# EEZ_PSU_post-regulator_r4B44_SS.net
KiCad netlist of a schematic drawn in EAGLE
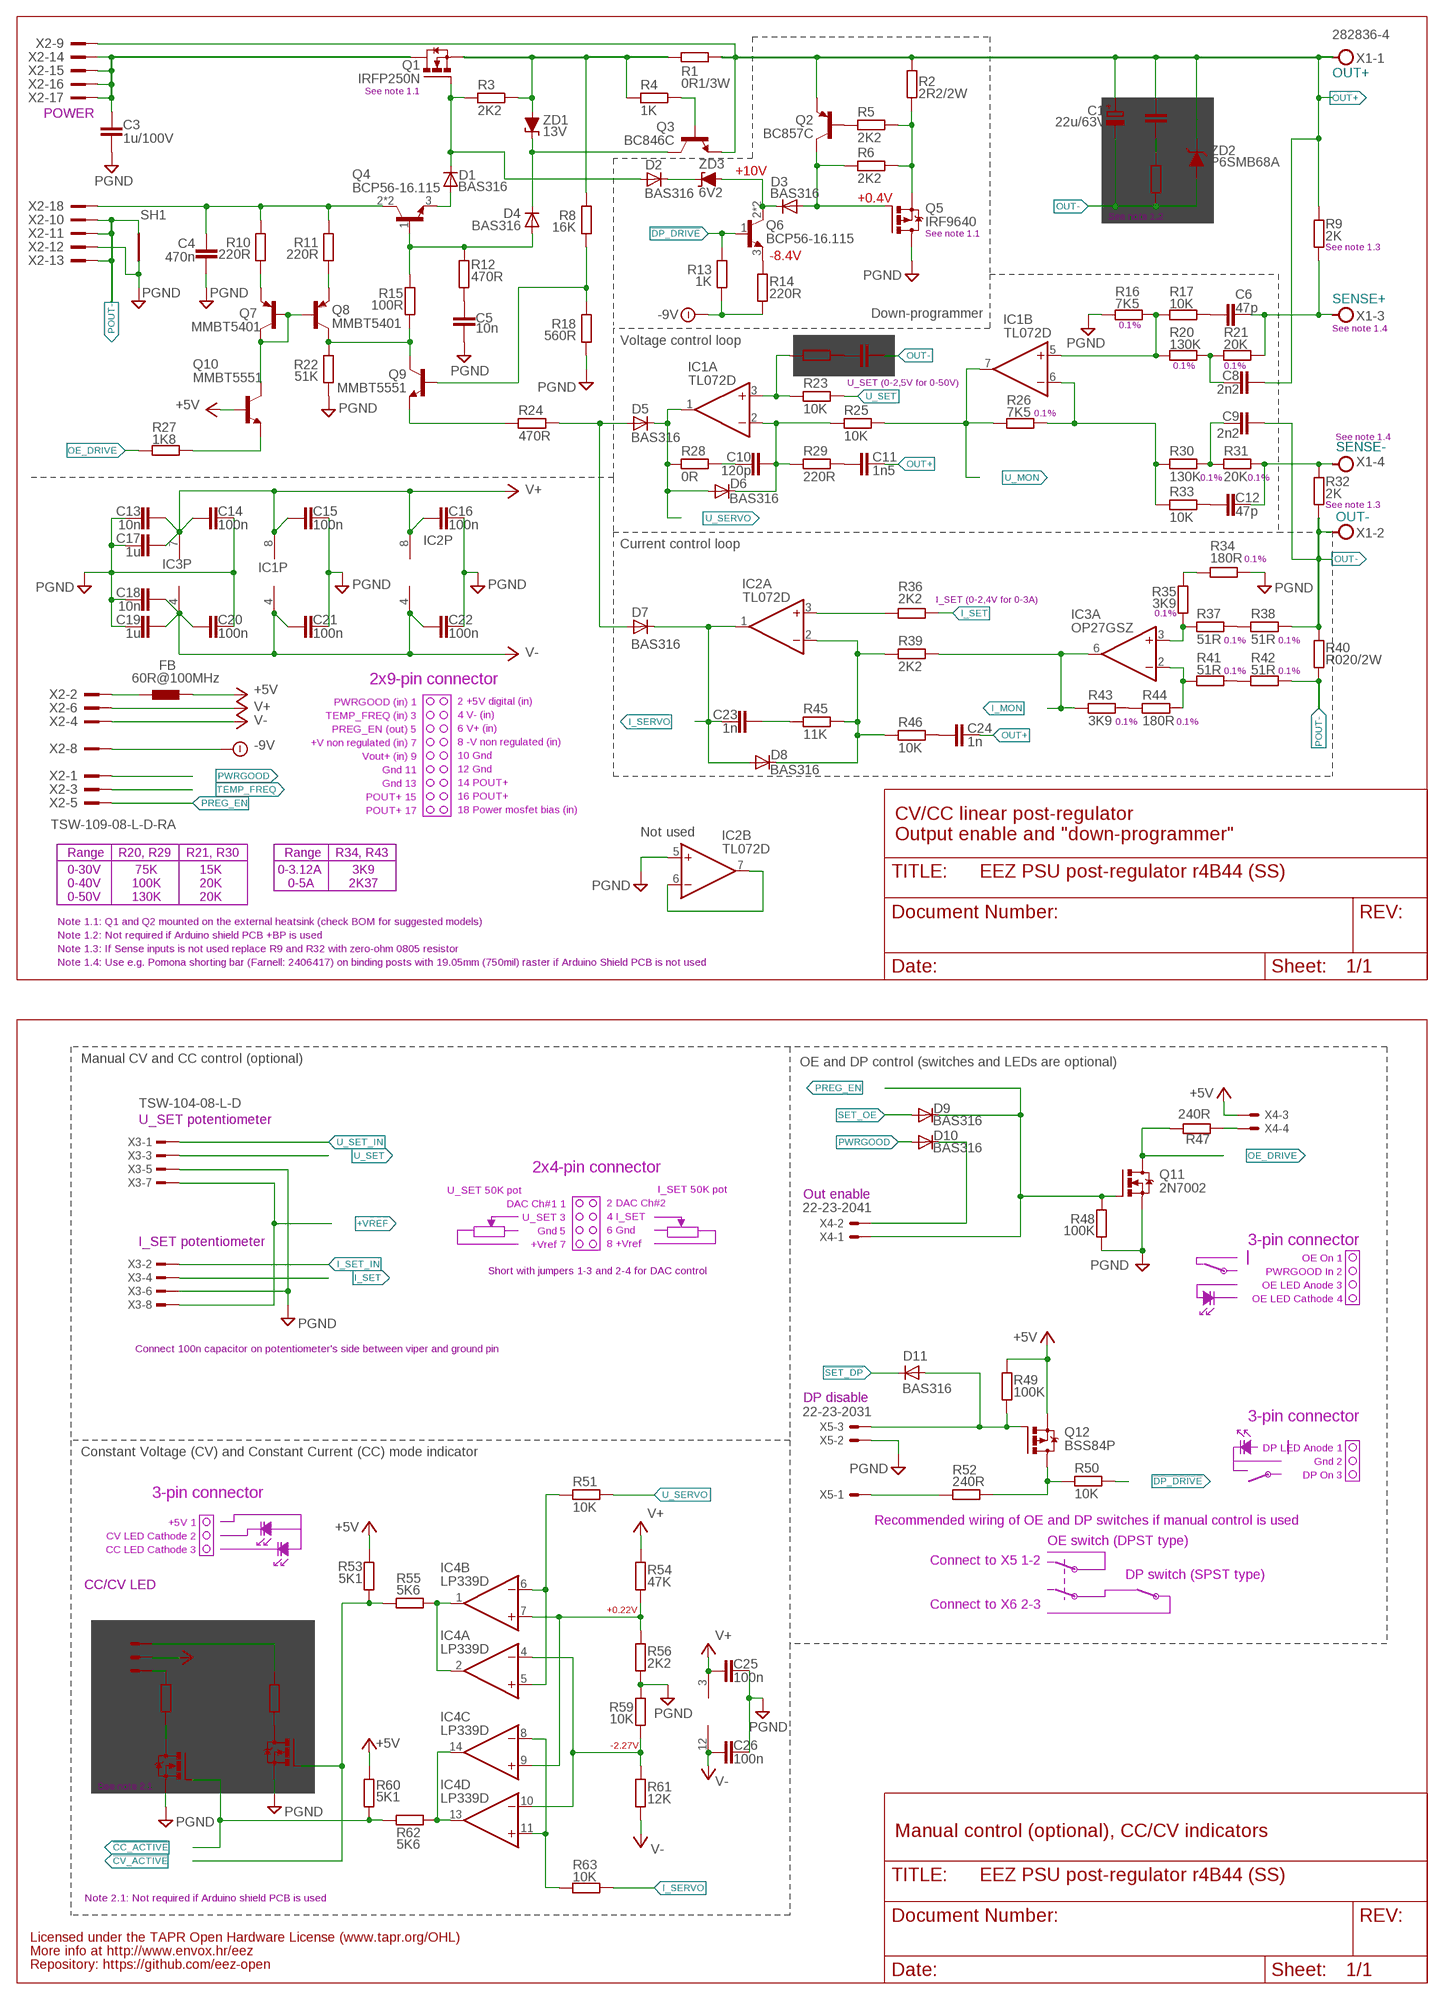
[diagram p0: schematic, sheet 1, part 1 of 2]
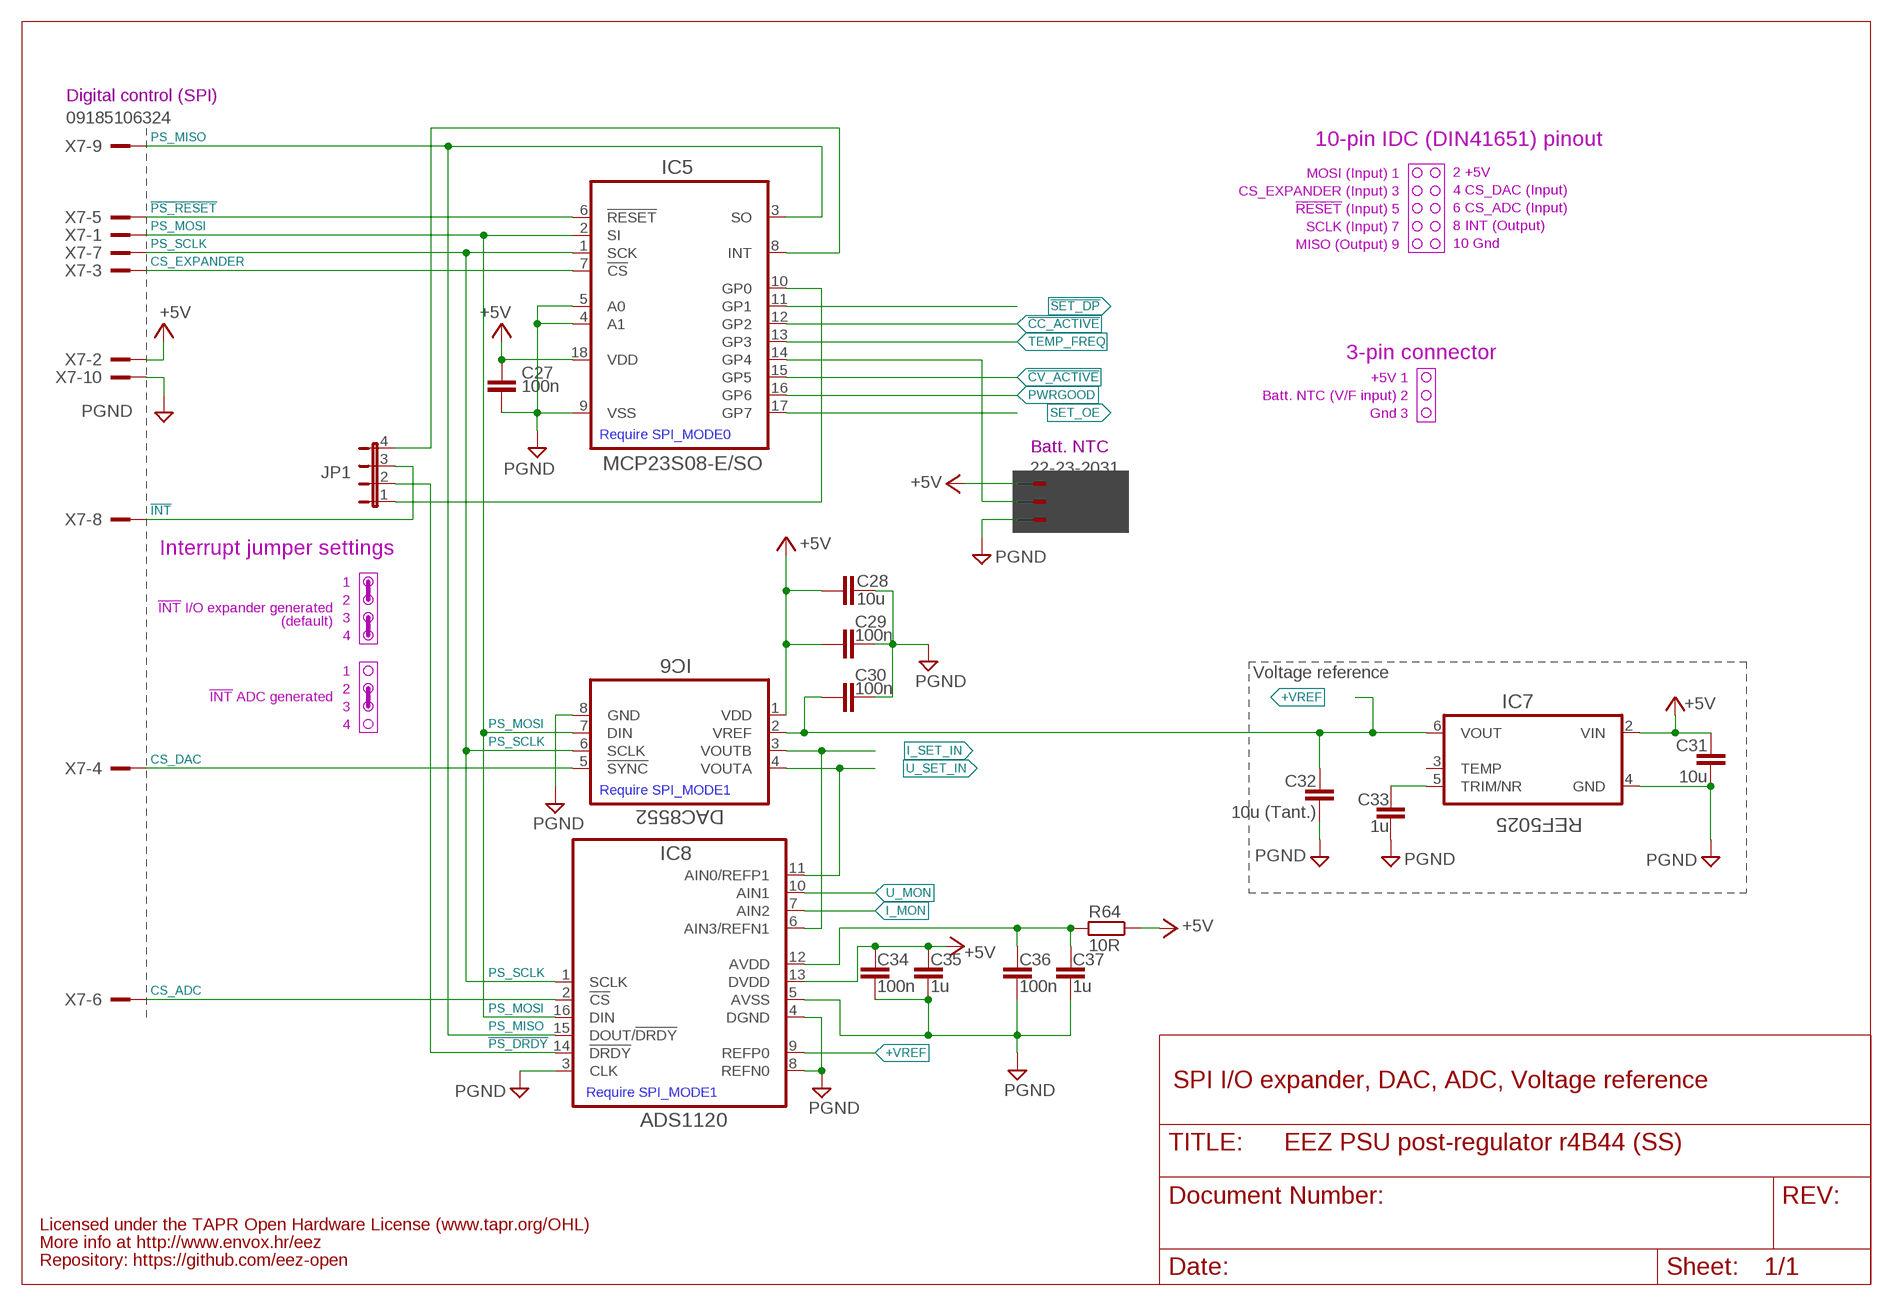
[diagram p1: schematic, sheet 1, part 2 of 2]

(export (version "E")
  (design (tool "Eeschema 10.0.6"))
  (components
    (comp (ref "C1")
      (value "22u/63V")
      (footprint "eagle-import:CAPAE660X610N_COMBO2")
      (libsource (lib "eagle-import") (part "ECAPEEEFK+2.5MM"))
    )
    (comp (ref "C2")
      (value "470n")
      (footprint "eagle-import:C1812")
      (libsource (lib "eagle-import") (part "C-EUC1812"))
    )
    (comp (ref "C3")
      (value "1u/100V")
      (footprint "eagle-import:C1206")
      (libsource (lib "eagle-import") (part "C-EUC1206"))
    )
    (comp (ref "C4")
      (value "470n")
      (footprint "eagle-import:C1812")
      (libsource (lib "eagle-import") (part "C-EUC1812"))
    )
    (comp (ref "C5")
      (value "10n")
      (footprint "eagle-import:C0805")
      (libsource (lib "eagle-import") (part "C-EUC0805"))
    )
    (comp (ref "C6")
      (value "47p")
      (footprint "eagle-import:C0805")
      (libsource (lib "eagle-import") (part "C-EUC0805"))
    )
    (comp (ref "C7")
      (value "1n5")
      (footprint "eagle-import:C0805")
      (libsource (lib "eagle-import") (part "C-EUC0805"))
    )
    (comp (ref "C8")
      (value "2n2")
      (footprint "eagle-import:C0805")
      (libsource (lib "eagle-import") (part "C-EUC0805"))
    )
    (comp (ref "C9")
      (value "2n2")
      (footprint "eagle-import:C0805")
      (libsource (lib "eagle-import") (part "C-EUC0805"))
    )
    (comp (ref "C10")
      (value "120p")
      (footprint "eagle-import:C0805")
      (libsource (lib "eagle-import") (part "C-EUC0805"))
    )
    (comp (ref "C11")
      (value "1n5")
      (footprint "eagle-import:C0805")
      (libsource (lib "eagle-import") (part "C-EUC0805"))
    )
    (comp (ref "C12")
      (value "47p")
      (footprint "eagle-import:C0805")
      (libsource (lib "eagle-import") (part "C-EUC0805"))
    )
    (comp (ref "C13")
      (value "10n")
      (footprint "eagle-import:C0805")
      (libsource (lib "eagle-import") (part "C-EUC0805"))
    )
    (comp (ref "C14")
      (value "100n")
      (footprint "eagle-import:C0603")
      (libsource (lib "eagle-import") (part "C-EUC0603"))
    )
    (comp (ref "C15")
      (value "100n")
      (footprint "eagle-import:C0603")
      (libsource (lib "eagle-import") (part "C-EUC0603"))
    )
    (comp (ref "C16")
      (value "100n")
      (footprint "eagle-import:C0603")
      (libsource (lib "eagle-import") (part "C-EUC0603"))
    )
    (comp (ref "C17")
      (value "1u")
      (footprint "eagle-import:C0805")
      (libsource (lib "eagle-import") (part "C-EUC0805"))
    )
    (comp (ref "C18")
      (value "10n")
      (footprint "eagle-import:C0805")
      (libsource (lib "eagle-import") (part "C-EUC0805"))
    )
    (comp (ref "C19")
      (value "1u")
      (footprint "eagle-import:C0805")
      (libsource (lib "eagle-import") (part "C-EUC0805"))
    )
    (comp (ref "C20")
      (value "100n")
      (footprint "eagle-import:C0603")
      (libsource (lib "eagle-import") (part "C-EUC0603"))
    )
    (comp (ref "C21")
      (value "100n")
      (footprint "eagle-import:C0603")
      (libsource (lib "eagle-import") (part "C-EUC0603"))
    )
    (comp (ref "C22")
      (value "100n")
      (footprint "eagle-import:C0603")
      (libsource (lib "eagle-import") (part "C-EUC0603"))
    )
    (comp (ref "C23")
      (value "1n")
      (footprint "eagle-import:C0805")
      (libsource (lib "eagle-import") (part "C-EUC0805"))
    )
    (comp (ref "C24")
      (value "1n")
      (footprint "eagle-import:C0805")
      (libsource (lib "eagle-import") (part "C-EUC0805"))
    )
    (comp (ref "C25")
      (value "100n")
      (footprint "eagle-import:C0603")
      (libsource (lib "eagle-import") (part "C-EUC0603"))
    )
    (comp (ref "C26")
      (value "100n")
      (footprint "eagle-import:C0603")
      (libsource (lib "eagle-import") (part "C-EUC0603"))
    )
    (comp (ref "C27")
      (value "100n")
      (footprint "eagle-import:C0603")
      (libsource (lib "eagle-import") (part "C-EUC0603"))
    )
    (comp (ref "C28")
      (value "10u")
      (footprint "eagle-import:C1206")
      (libsource (lib "eagle-import") (part "C-EUC1206"))
    )
    (comp (ref "C29")
      (value "100n")
      (footprint "eagle-import:C0603")
      (libsource (lib "eagle-import") (part "C-EUC0603"))
    )
    (comp (ref "C30")
      (value "100n")
      (footprint "eagle-import:C0603")
      (libsource (lib "eagle-import") (part "C-EUC0603"))
    )
    (comp (ref "C31")
      (value "10u")
      (footprint "eagle-import:C1206")
      (libsource (lib "eagle-import") (part "C-EUC1206"))
    )
    (comp (ref "C32")
      (value "10u (Tant.)")
      (footprint "eagle-import:C1206")
      (libsource (lib "eagle-import") (part "C-EUC1206"))
    )
    (comp (ref "C33")
      (value "1u")
      (footprint "eagle-import:C0805")
      (libsource (lib "eagle-import") (part "C-EUC0805"))
    )
    (comp (ref "C34")
      (value "100n")
      (footprint "eagle-import:C0603")
      (libsource (lib "eagle-import") (part "C-EUC0603"))
    )
    (comp (ref "C35")
      (value "1u")
      (footprint "eagle-import:C0805")
      (libsource (lib "eagle-import") (part "C-EUC0805"))
    )
    (comp (ref "C36")
      (value "100n")
      (footprint "eagle-import:C0603")
      (libsource (lib "eagle-import") (part "C-EUC0603"))
    )
    (comp (ref "C37")
      (value "1u")
      (footprint "eagle-import:C0805")
      (libsource (lib "eagle-import") (part "C-EUC0805"))
    )
    (comp (ref "D1")
      (value "BAS316")
      (footprint "eagle-import:SOD323-W")
      (libsource (lib "eagle-import") (part "DIODE-SOD323-W"))
    )
    (comp (ref "D2")
      (value "BAS316")
      (footprint "eagle-import:SOD323-W")
      (libsource (lib "eagle-import") (part "DIODE-SOD323-W"))
    )
    (comp (ref "D3")
      (value "BAS316")
      (footprint "eagle-import:SOD323-W")
      (libsource (lib "eagle-import") (part "DIODE-SOD323-W"))
    )
    (comp (ref "D4")
      (value "BAS316")
      (footprint "eagle-import:SOD323-W")
      (libsource (lib "eagle-import") (part "DIODE-SOD323-W"))
    )
    (comp (ref "D5")
      (value "BAS316")
      (footprint "eagle-import:SOD323-W")
      (libsource (lib "eagle-import") (part "DIODE-SOD323-W"))
    )
    (comp (ref "D6")
      (value "BAS316")
      (footprint "eagle-import:SOD323-W")
      (libsource (lib "eagle-import") (part "DIODE-SOD323-W"))
    )
    (comp (ref "D7")
      (value "BAS316")
      (footprint "eagle-import:SOD323-W")
      (libsource (lib "eagle-import") (part "DIODE-SOD323-W"))
    )
    (comp (ref "D8")
      (value "BAS316")
      (footprint "eagle-import:SOD323-W")
      (libsource (lib "eagle-import") (part "DIODE-SOD323-W"))
    )
    (comp (ref "D9")
      (value "BAS316")
      (footprint "eagle-import:SOD323-W")
      (libsource (lib "eagle-import") (part "DIODE-SOD323-W"))
    )
    (comp (ref "D10")
      (value "BAS316")
      (footprint "eagle-import:SOD323-W")
      (libsource (lib "eagle-import") (part "DIODE-SOD323-W"))
    )
    (comp (ref "D11")
      (value "BAS316")
      (footprint "eagle-import:SOD323-W")
      (libsource (lib "eagle-import") (part "DIODE-SOD323-W"))
    )
    (comp (ref "FB")
      (value "60R@100MHz")
      (footprint "eagle-import:BEAD0603")
      (libsource (lib "eagle-import") (part "FERRITE_BEAD0603"))
    )
    (comp (ref "IC1")
      (value "TL072D")
      (footprint "eagle-import:SOIC127P600X173-8N")
      (libsource (lib "eagle-import") (part "TL072SOIC8"))
    )
    (comp (ref "IC2")
      (value "TL072D")
      (footprint "eagle-import:SOIC127P600X173-8N")
      (libsource (lib "eagle-import") (part "TL072SOIC8"))
    )
    (comp (ref "IC3")
      (value "OP27GSZ")
      (footprint "eagle-import:SOIC127P600X173-8N")
      (libsource (lib "eagle-import") (part "OP27GSZSO8"))
    )
    (comp (ref "IC4")
      (value "LP339D")
      (footprint "eagle-import:SO14")
      (libsource (lib "eagle-import") (part "LM339D"))
    )
    (comp (ref "IC5")
      (value "MCP23S08-E/SO")
      (footprint "eagle-import:SOIC127P1030X265-18N")
      (libsource (lib "eagle-import") (part "MCP23S08"))
    )
    (comp (ref "IC6")
      (value "DAC8552")
      (footprint "eagle-import:DGK8-M")
      (libsource (lib "eagle-import") (part "DAC8552_DGK_8M"))
    )
    (comp (ref "IC7")
      (value "REF5025")
      (footprint "eagle-import:SOIC127P600X175-8N")
      (libsource (lib "eagle-import") (part "REF50XX"))
    )
    (comp (ref "IC8")
      (value "ADS1120")
      (footprint "eagle-import:PW(R-PDSO-G16)")
      (libsource (lib "eagle-import") (part "ADS1120TSSOP-16"))
    )
    (comp (ref "JP1")
      (value "JP4E")
      (footprint "eagle-import:JP4")
      (libsource (lib "eagle-import") (part "JP4E"))
    )
    (comp (ref "Q1")
      (value "IRFP250N")
      (footprint "eagle-import:TO247BV")
      (libsource (lib "eagle-import") (part "IRFP240"))
    )
    (comp (ref "Q2")
      (value "BC857C")
      (footprint "eagle-import:SOT23-BEC")
      (libsource (lib "eagle-import") (part "-PNP-SOT23-BECBC857C"))
    )
    (comp (ref "Q3")
      (value "BC846C")
      (footprint "eagle-import:SOT23-BEC")
      (libsource (lib "eagle-import") (part "-NPN-SOT23-BECBC846B"))
    )
    (comp (ref "Q4")
      (value "BCP56-16.115")
      (footprint "eagle-import:SOT230P700X180-4N")
      (libsource (lib "eagle-import") (part "BCP56"))
    )
    (comp (ref "Q5")
      (value "IRF9640")
      (footprint "eagle-import:TO220B-VMOS")
      (libsource (lib "eagle-import") (part "IRF9640"))
    )
    (comp (ref "Q6")
      (value "BCP56-16.115")
      (footprint "eagle-import:SOT230P700X180-4N")
      (libsource (lib "eagle-import") (part "BCP56"))
    )
    (comp (ref "Q7")
      (value "MMBT5401")
      (footprint "eagle-import:SOT23-BEC")
      (libsource (lib "eagle-import") (part "-PNP-SOT23-BECBC857B"))
    )
    (comp (ref "Q8")
      (value "MMBT5401")
      (footprint "eagle-import:SOT23-BEC")
      (libsource (lib "eagle-import") (part "-PNP-SOT23-BECBC857B"))
    )
    (comp (ref "Q9")
      (value "MMBT5551")
      (footprint "eagle-import:SOT23-BEC")
      (libsource (lib "eagle-import") (part "-NPN-SOT23-BECMMBT5551LT1"))
    )
    (comp (ref "Q10")
      (value "MMBT5551")
      (footprint "eagle-import:SOT23-BEC")
      (libsource (lib "eagle-import") (part "-NPN-SOT23-BECMMBT5551LT1"))
    )
    (comp (ref "Q11")
      (value "2N7002")
      (footprint "eagle-import:SOT103P240X110-3N")
      (fields
        (field (name "MPN") "2N7002-7-F")
        (field (name "MPN_1") "2N7002-7-F")
        (field (name "OC_FARNELL") "1713823")
        (field (name "OC_NEWARK") "25R5679")
        (field (name "PACKAGE") "SOT-23-3")
        (field (name "SUPPLIER") "DIODES INC.")
      )
      (libsource (lib "eagle-import") (part "2N7002"))
    )
    (comp (ref "Q12")
      (value "BSS84P")
      (footprint "eagle-import:SOT95P237X112-3N")
      (fields (field (name "MPN") "IRLML2246TRPBF"))
      (libsource (lib "eagle-import") (part "IRLML2246TRPBF"))
    )
    (comp (ref "Q13")
      (value "2N7002")
      (footprint "eagle-import:SOT103P240X110-3N")
      (fields (field (name "MPN") "2N7002-7-F"))
      (libsource (lib "eagle-import") (part "2N7002"))
    )
    (comp (ref "Q14")
      (value "2N7002")
      (footprint "eagle-import:SOT103P240X110-3N")
      (fields (field (name "MPN") "2N7002-7-F"))
      (libsource (lib "eagle-import") (part "2N7002"))
    )
    (comp (ref "R1")
      (value "0R1/3W")
      (footprint "eagle-import:0411V")
      (libsource (lib "eagle-import") (part "R-EU_0411/3V"))
    )
    (comp (ref "R2")
      (value "2R2/2W")
      (footprint "eagle-import:0411V")
      (libsource (lib "eagle-import") (part "R-EU_0411/3V"))
    )
    (comp (ref "R3")
      (value "2K2")
      (footprint "eagle-import:R0805")
      (libsource (lib "eagle-import") (part "R-EU_R0805"))
    )
    (comp (ref "R4")
      (value "1K")
      (footprint "eagle-import:R0805")
      (libsource (lib "eagle-import") (part "R-EU_R0805"))
    )
    (comp (ref "R5")
      (value "2K2")
      (footprint "eagle-import:R0805")
      (libsource (lib "eagle-import") (part "R-EU_R0805"))
    )
    (comp (ref "R6")
      (value "2K2")
      (footprint "eagle-import:R0805")
      (libsource (lib "eagle-import") (part "R-EU_R0805"))
    )
    (comp (ref "R7")
      (value "1R")
      (footprint "eagle-import:R0805")
      (libsource (lib "eagle-import") (part "R-EU_R0805"))
    )
    (comp (ref "R8")
      (value "16K")
      (footprint "eagle-import:R0805")
      (libsource (lib "eagle-import") (part "R-EU_R0805"))
    )
    (comp (ref "R9")
      (value "2K")
      (footprint "eagle-import:R0805")
      (libsource (lib "eagle-import") (part "R-EU_R0805"))
    )
    (comp (ref "R10")
      (value "220R")
      (footprint "eagle-import:R0805")
      (libsource (lib "eagle-import") (part "R-EU_R0805"))
    )
    (comp (ref "R11")
      (value "220R")
      (footprint "eagle-import:R0805")
      (libsource (lib "eagle-import") (part "R-EU_R0805"))
    )
    (comp (ref "R12")
      (value "470R")
      (footprint "eagle-import:R0805")
      (libsource (lib "eagle-import") (part "R-EU_R0805"))
    )
    (comp (ref "R13")
      (value "1K")
      (footprint "eagle-import:R0805")
      (libsource (lib "eagle-import") (part "R-EU_R0805"))
    )
    (comp (ref "R14")
      (value "220R")
      (footprint "eagle-import:R0805")
      (libsource (lib "eagle-import") (part "R-EU_R0805"))
    )
    (comp (ref "R15")
      (value "100R")
      (footprint "eagle-import:R0805")
      (libsource (lib "eagle-import") (part "R-EU_R0805"))
    )
    (comp (ref "R16")
      (value "7K5")
      (footprint "eagle-import:R0805")
      (libsource (lib "eagle-import") (part "R-EU_R0805"))
    )
    (comp (ref "R17")
      (value "10K")
      (footprint "eagle-import:R0805")
      (libsource (lib "eagle-import") (part "R-EU_R0805"))
    )
    (comp (ref "R18")
      (value "560R")
      (footprint "eagle-import:R0805")
      (libsource (lib "eagle-import") (part "R-EU_R0805"))
    )
    (comp (ref "R19")
      (value "220R")
      (footprint "eagle-import:R0805")
      (libsource (lib "eagle-import") (part "R-EU_R0805"))
    )
    (comp (ref "R20")
      (value "130K")
      (footprint "eagle-import:R0805")
      (libsource (lib "eagle-import") (part "R-EU_R0805"))
    )
    (comp (ref "R21")
      (value "20K")
      (footprint "eagle-import:R0805")
      (libsource (lib "eagle-import") (part "R-EU_R0805"))
    )
    (comp (ref "R22")
      (value "51K")
      (footprint "eagle-import:R0805")
      (libsource (lib "eagle-import") (part "R-EU_R0805"))
    )
    (comp (ref "R23")
      (value "10K")
      (footprint "eagle-import:R0805")
      (libsource (lib "eagle-import") (part "R-EU_R0805"))
    )
    (comp (ref "R24")
      (value "470R")
      (footprint "eagle-import:R0805")
      (libsource (lib "eagle-import") (part "R-EU_R0805"))
    )
    (comp (ref "R25")
      (value "10K")
      (footprint "eagle-import:R0805")
      (libsource (lib "eagle-import") (part "R-EU_R0805"))
    )
    (comp (ref "R26")
      (value "7K5")
      (footprint "eagle-import:R0805")
      (libsource (lib "eagle-import") (part "R-EU_R0805"))
    )
    (comp (ref "R27")
      (value "1K8")
      (footprint "eagle-import:R0805")
      (libsource (lib "eagle-import") (part "R-EU_R0805"))
    )
    (comp (ref "R28")
      (value "0R")
      (footprint "eagle-import:R0805")
      (libsource (lib "eagle-import") (part "R-EU_R0805"))
    )
    (comp (ref "R29")
      (value "220R")
      (footprint "eagle-import:R0805")
      (libsource (lib "eagle-import") (part "R-EU_R0805"))
    )
    (comp (ref "R30")
      (value "130K")
      (footprint "eagle-import:R0805")
      (libsource (lib "eagle-import") (part "R-EU_R0805"))
    )
    (comp (ref "R31")
      (value "20K")
      (footprint "eagle-import:R0805")
      (libsource (lib "eagle-import") (part "R-EU_R0805"))
    )
    (comp (ref "R32")
      (value "2K")
      (footprint "eagle-import:R0805")
      (libsource (lib "eagle-import") (part "R-EU_R0805"))
    )
    (comp (ref "R33")
      (value "10K")
      (footprint "eagle-import:R0805")
      (libsource (lib "eagle-import") (part "R-EU_R0805"))
    )
    (comp (ref "R34")
      (value "180R")
      (footprint "eagle-import:R0805")
      (libsource (lib "eagle-import") (part "R-EU_R0805"))
    )
    (comp (ref "R35")
      (value "3K9")
      (footprint "eagle-import:R0805")
      (libsource (lib "eagle-import") (part "R-EU_R0805"))
    )
    (comp (ref "R36")
      (value "2K2")
      (footprint "eagle-import:R0805")
      (libsource (lib "eagle-import") (part "R-EU_R0805"))
    )
    (comp (ref "R37")
      (value "51R")
      (footprint "eagle-import:R0805")
      (libsource (lib "eagle-import") (part "R-EU_R0805"))
    )
    (comp (ref "R38")
      (value "51R")
      (footprint "eagle-import:R0805")
      (libsource (lib "eagle-import") (part "R-EU_R0805"))
    )
    (comp (ref "R39")
      (value "2K2")
      (footprint "eagle-import:R0805")
      (libsource (lib "eagle-import") (part "R-EU_R0805"))
    )
    (comp (ref "R40")
      (value "R020/2W")
      (footprint "eagle-import:R2512")
      (libsource (lib "eagle-import") (part "R-EU_R2512"))
    )
    (comp (ref "R41")
      (value "51R")
      (footprint "eagle-import:R0805")
      (libsource (lib "eagle-import") (part "R-EU_R0805"))
    )
    (comp (ref "R42")
      (value "51R")
      (footprint "eagle-import:R0805")
      (libsource (lib "eagle-import") (part "R-EU_R0805"))
    )
    (comp (ref "R43")
      (value "3K9")
      (footprint "eagle-import:R0805")
      (libsource (lib "eagle-import") (part "R-EU_R0805"))
    )
    (comp (ref "R44")
      (value "180R")
      (footprint "eagle-import:R0805")
      (libsource (lib "eagle-import") (part "R-EU_R0805"))
    )
    (comp (ref "R45")
      (value "11K")
      (footprint "eagle-import:R0805")
      (libsource (lib "eagle-import") (part "R-EU_R0805"))
    )
    (comp (ref "R46")
      (value "10K")
      (footprint "eagle-import:R0805")
      (libsource (lib "eagle-import") (part "R-EU_R0805"))
    )
    (comp (ref "R47")
      (value "240R")
      (footprint "eagle-import:R0805")
      (libsource (lib "eagle-import") (part "R-EU_R0805"))
    )
    (comp (ref "R48")
      (value "100K")
      (footprint "eagle-import:R0805")
      (libsource (lib "eagle-import") (part "R-EU_R0805"))
    )
    (comp (ref "R49")
      (value "100K")
      (footprint "eagle-import:R0805")
      (libsource (lib "eagle-import") (part "R-EU_R0805"))
    )
    (comp (ref "R50")
      (value "10K")
      (footprint "eagle-import:R0805")
      (libsource (lib "eagle-import") (part "R-EU_R0805"))
    )
    (comp (ref "R51")
      (value "10K")
      (footprint "eagle-import:R0805")
      (libsource (lib "eagle-import") (part "R-EU_R0805"))
    )
    (comp (ref "R52")
      (value "240R")
      (footprint "eagle-import:R0805")
      (libsource (lib "eagle-import") (part "R-EU_R0805"))
    )
    (comp (ref "R53")
      (value "5K1")
      (footprint "eagle-import:R0805")
      (libsource (lib "eagle-import") (part "R-EU_R0805"))
    )
    (comp (ref "R54")
      (value "47K")
      (footprint "eagle-import:R0805")
      (libsource (lib "eagle-import") (part "R-EU_R0805"))
    )
    (comp (ref "R55")
      (value "5K6")
      (footprint "eagle-import:R0805")
      (libsource (lib "eagle-import") (part "R-EU_R0805"))
    )
    (comp (ref "R56")
      (value "2K2")
      (footprint "eagle-import:R0805")
      (libsource (lib "eagle-import") (part "R-EU_R0805"))
    )
    (comp (ref "R57")
      (value "240R")
      (footprint "eagle-import:R0805")
      (libsource (lib "eagle-import") (part "R-EU_R0805"))
    )
    (comp (ref "R58")
      (value "240R")
      (footprint "eagle-import:R0805")
      (libsource (lib "eagle-import") (part "R-EU_R0805"))
    )
    (comp (ref "R59")
      (value "10K")
      (footprint "eagle-import:R0805")
      (libsource (lib "eagle-import") (part "R-EU_R0805"))
    )
    (comp (ref "R60")
      (value "5K1")
      (footprint "eagle-import:R0805")
      (libsource (lib "eagle-import") (part "R-EU_R0805"))
    )
    (comp (ref "R61")
      (value "12K")
      (footprint "eagle-import:R0805")
      (libsource (lib "eagle-import") (part "R-EU_R0805"))
    )
    (comp (ref "R62")
      (value "5K6")
      (footprint "eagle-import:R0805")
      (libsource (lib "eagle-import") (part "R-EU_R0805"))
    )
    (comp (ref "R63")
      (value "10K")
      (footprint "eagle-import:R0805")
      (libsource (lib "eagle-import") (part "R-EU_R0805"))
    )
    (comp (ref "R64")
      (value "10R")
      (footprint "eagle-import:R0805")
      (libsource (lib "eagle-import") (part "R-EU_R0805"))
    )
    (comp (ref "SH1")
      (value "GND")
      (footprint "eagle-import:SHORT")
      (libsource (lib "eagle-import") (part "SHORT"))
    )
    (comp (ref "X1")
      (value "282836-4")
      (footprint "eagle-import:TBLOCK5.0_4")
      (libsource (lib "eagle-import") (part "TBLOCK5.0_4A"))
    )
    (comp (ref "X2")
      (value "TSW-109-08-L-D-RA")
      (footprint "eagle-import:TSW-109-08-L-D-RA")
      (fields (field (name "FARNELL") "2032801"))
      (libsource (lib "eagle-import") (part "TSW-109-08-L-D-RA"))
    )
    (comp (ref "X3")
      (value "TSW-104-08-L-D")
      (footprint "eagle-import:TSW-104-02-S-D")
      (libsource (lib "eagle-import") (part "TSW-104-02-S-D"))
    )
    (comp (ref "X4")
      (value "22-23-2041")
      (footprint "eagle-import:22-23-2041")
      (fields
        (field (name "MF") "MOLEX")
        (field (name "MPN") "22-23-2041")
        (field (name "OC_FARNELL") "1462920")
        (field (name "OC_NEWARK") "38C0355")
      )
      (libsource (lib "eagle-import") (part "22-23-2041"))
    )
    (comp (ref "X5")
      (value "22-23-2031")
      (footprint "eagle-import:22-23-2031")
      (fields
        (field (name "MF") "MOLEX")
        (field (name "MF_1") "MOLEX")
        (field (name "MPN") "22-23-2031")
        (field (name "OC_FARNELL") "1462950")
        (field (name "OC_NEWARK") "30C0862")
      )
      (libsource (lib "eagle-import") (part "22-23-2031"))
    )
    (comp (ref "X6")
      (value "22-23-2031")
      (footprint "eagle-import:22-23-2031")
      (fields
        (field (name "MF") "MOLEX")
        (field (name "MPN") "22-23-2031")
        (field (name "OC_FARNELL") "1462950")
        (field (name "OC_NEWARK") "30C0862")
      )
      (libsource (lib "eagle-import") (part "22-23-2031"))
    )
    (comp (ref "X7")
      (value "09185106324")
      (footprint "eagle-import:PAK100_2500-10")
      (fields (field (name "MF") "3M") (field (name "MPN") "2510-6002UB"))
      (libsource (lib "eagle-import") (part "2510-"))
    )
    (comp (ref "X8")
      (value "22-23-2031")
      (footprint "eagle-import:22-23-2031")
      (fields
        (field (name "MF") "MOLEX")
        (field (name "MPN") "22-23-2031")
        (field (name "OC_FARNELL") "1462950")
        (field (name "OC_NEWARK") "30C0862")
      )
      (libsource (lib "eagle-import") (part "22-23-2031"))
    )
    (comp (ref "ZD1")
      (value "13V")
      (footprint "eagle-import:MINIMELF")
      (libsource (lib "eagle-import") (part "ZENER-DIODEMINIMELF"))
    )
    (comp (ref "ZD2")
      (value "P6SMB68A")
      (footprint "eagle-import:DO214AA")
      (libsource (lib "eagle-import") (part "P6SMB68A"))
    )
    (comp (ref "ZD3")
      (value "6V2")
      (footprint "eagle-import:MINIMELF")
      (libsource (lib "eagle-import") (part "ZENER-DIODEMINIMELF"))
    )
  )
  (nets
    (net (code "1") (name "+5V") (class "Default")
      (node (ref "C27") (pin "1") (pinfunction "1_1") (pintype "passive"))
      (node (ref "C28") (pin "1") (pinfunction "1_1") (pintype "passive"))
      (node (ref "C29") (pin "2") (pinfunction "2_2") (pintype "passive"))
      (node (ref "C31") (pin "1") (pinfunction "1_1") (pintype "passive"))
      (node (ref "C34") (pin "2") (pinfunction "2_2") (pintype "passive"))
      (node (ref "C35") (pin "2") (pinfunction "2_2") (pintype "passive"))
      (node (ref "FB") (pin "P$2") (pinfunction "2_P$2") (pintype "passive"))
      (node (ref "IC5") (pin "18") (pinfunction "VDD_18") (pintype "power_in"))
      (node (ref "IC6") (pin "1") (pinfunction "VDD_1") (pintype "power_in"))
      (node (ref "IC7") (pin "2") (pinfunction "VIN_2") (pintype "passive"))
      (node (ref "IC8") (pin "13") (pinfunction "DVDD_13") (pintype "power_in"))
      (node (ref "Q10") (pin "B") (pinfunction "B_B") (pintype "passive"))
      (node (ref "Q12") (pin "2") (pinfunction "S_2") (pintype "passive"))
      (node (ref "R49") (pin "1") (pinfunction "1_1") (pintype "passive"))
      (node (ref "R53") (pin "2") (pinfunction "2_2") (pintype "passive"))
      (node (ref "R60") (pin "2") (pinfunction "2_2") (pintype "passive"))
      (node (ref "R64") (pin "1") (pinfunction "1_1") (pintype "passive"))
      (node (ref "X4") (pin "3") (pinfunction "S_3") (pintype "passive"))
      (node (ref "X6") (pin "2") (pinfunction "S_2") (pintype "passive"))
      (node (ref "X7") (pin "2") (pinfunction "KL_2") (pintype "passive"))
      (node (ref "X8") (pin "1") (pinfunction "S_1") (pintype "passive"))
    )
    (net (code "2") (name "+VREF") (class "Default")
      (node (ref "C30") (pin "2") (pinfunction "2_2") (pintype "passive"))
      (node (ref "C32") (pin "1") (pinfunction "1_1") (pintype "passive"))
      (node (ref "IC6") (pin "2") (pinfunction "VREF_2") (pintype "input"))
      (node (ref "IC7") (pin "6") (pinfunction "VOUT_6") (pintype "output"))
      (node (ref "IC8") (pin "9") (pinfunction "REFP0_9") (pintype "input"))
      (node (ref "X3") (pin "7") (pinfunction "1_7") (pintype "passive"))
      (node (ref "X3") (pin "8") (pinfunction "1_8") (pintype "passive"))
    )
    (net (code "3") (name "-9V") (class "Default")
      (node (ref "R13") (pin "2") (pinfunction "2_2") (pintype "passive"))
      (node (ref "R14") (pin "2") (pinfunction "2_2") (pintype "passive"))
      (node (ref "X2") (pin "8") (pinfunction "KL_8") (pintype "passive"))
    )
    (net (code "4") (name "/CS_ADC") (class "Default")
      (node (ref "IC8") (pin "2") (pinfunction "~{CS}_2") (pintype "input"))
      (node (ref "X7") (pin "6") (pinfunction "KL_6") (pintype "passive"))
    )
    (net (code "5") (name "/CS_DAC") (class "Default")
      (node (ref "IC6") (pin "5") (pinfunction "~{SYNC}_5") (pintype "input"))
      (node (ref "X7") (pin "4") (pinfunction "KL_4") (pintype "passive"))
    )
    (net (code "6") (name "/CS_EXPANDER") (class "Default")
      (node (ref "IC5") (pin "7") (pinfunction "~{CS}_7") (pintype "input"))
      (node (ref "X7") (pin "3") (pinfunction "KL_3") (pintype "passive"))
    )
    (net (code "7") (name "/PS_MISO") (class "Default")
      (node (ref "IC5") (pin "3") (pinfunction "SO_3") (pintype "output"))
      (node (ref "IC8") (pin "15") (pinfunction "DOUT/~{DRDY}_15") (pintype "output"))
      (node (ref "X7") (pin "9") (pinfunction "KL_9") (pintype "passive"))
    )
    (net (code "8") (name "/PS_MOSI") (class "Default")
      (node (ref "IC5") (pin "2") (pinfunction "SI_2") (pintype "input"))
      (node (ref "IC6") (pin "7") (pinfunction "DIN_7") (pintype "input"))
      (node (ref "IC8") (pin "16") (pinfunction "DIN_16") (pintype "input"))
      (node (ref "X7") (pin "1") (pinfunction "KL_1") (pintype "passive"))
    )
    (net (code "9") (name "/PS_SCLK") (class "Default")
      (node (ref "IC5") (pin "1") (pinfunction "SCK_1") (pintype "input"))
      (node (ref "IC6") (pin "6") (pinfunction "SCLK_6") (pintype "input"))
      (node (ref "IC8") (pin "1") (pinfunction "SCLK_1") (pintype "input"))
      (node (ref "X7") (pin "7") (pinfunction "KL_7") (pintype "passive"))
    )
    (net (code "10") (name "/SENSE+") (class "Default")
      (node (ref "C6") (pin "1") (pinfunction "1_1") (pintype "passive"))
      (node (ref "R21") (pin "2") (pinfunction "2_2") (pintype "passive"))
      (node (ref "R9") (pin "2") (pinfunction "2_2") (pintype "passive"))
      (node (ref "X1") (pin "P$3") (pinfunction "1_P$3") (pintype "bidirectional"))
    )
    (net (code "11") (name "/SENSE-") (class "Default")
      (node (ref "C12") (pin "1") (pinfunction "1_1") (pintype "passive"))
      (node (ref "R31") (pin "2") (pinfunction "2_2") (pintype "passive"))
      (node (ref "R32") (pin "1") (pinfunction "1_1") (pintype "passive"))
      (node (ref "X1") (pin "P$4") (pinfunction "1_P$4") (pintype "bidirectional"))
    )
    (net (code "12") (name "/~{CC_ACTIVE}") (class "Default")
      (node (ref "IC5") (pin "12") (pinfunction "GP2_12") (pintype "bidirectional"))
      (node (ref "Q14") (pin "1") (pinfunction "G_1") (pintype "passive"))
      (node (ref "R60") (pin "1") (pinfunction "1_1") (pintype "passive"))
      (node (ref "R62") (pin "2") (pinfunction "2_2") (pintype "passive"))
    )
    (net (code "13") (name "/~{CV_ACTIVE}") (class "Default")
      (node (ref "IC5") (pin "15") (pinfunction "GP5_15") (pintype "bidirectional"))
      (node (ref "Q13") (pin "1") (pinfunction "G_1") (pintype "passive"))
      (node (ref "R53") (pin "1") (pinfunction "1_1") (pintype "passive"))
      (node (ref "R55") (pin "2") (pinfunction "2_2") (pintype "passive"))
    )
    (net (code "14") (name "/~{DP_DRIVE}") (class "Default")
      (node (ref "Q6") (pin "1") (pinfunction "B_1") (pintype "passive"))
      (node (ref "R13") (pin "1") (pinfunction "1_1") (pintype "passive"))
      (node (ref "R50") (pin "1") (pinfunction "1_1") (pintype "passive"))
    )
    (net (code "15") (name "/~{INT}") (class "Default")
      (node (ref "JP1") (pin "3") (pinfunction "3_3") (pintype "passive"))
      (node (ref "X7") (pin "8") (pinfunction "KL_8") (pintype "passive"))
    )
    (net (code "16") (name "/~{PS_DRDY}") (class "Default")
      (node (ref "IC8") (pin "14") (pinfunction "~{DRDY}_14") (pintype "output"))
      (node (ref "JP1") (pin "2") (pinfunction "2_2") (pintype "passive"))
    )
    (net (code "17") (name "/~{PS_RESET}") (class "Default")
      (node (ref "IC5") (pin "6") (pinfunction "~{RESET}_6") (pintype "input"))
      (node (ref "X7") (pin "5") (pinfunction "KL_5") (pintype "passive"))
    )
    (net (code "18") (name "/~{SET_DP}") (class "Default")
      (node (ref "D11") (pin "C") (pinfunction "C_C") (pintype "passive"))
      (node (ref "IC5") (pin "11") (pinfunction "GP1_11") (pintype "bidirectional"))
    )
    (net (code "19") (name "I_MON") (class "Default")
      (node (ref "IC3") (pin "6") (pinfunction "OUT_6") (pintype "output"))
      (node (ref "IC8") (pin "7") (pinfunction "AIN2_7") (pintype "input"))
      (node (ref "R39") (pin "1") (pinfunction "1_1") (pintype "passive"))
      (node (ref "R43") (pin "2") (pinfunction "2_2") (pintype "passive"))
    )
    (net (code "20") (name "I_SERVO") (class "Default")
      (node (ref "C23") (pin "2") (pinfunction "2_2") (pintype "passive"))
      (node (ref "D7") (pin "C") (pinfunction "C_C") (pintype "passive"))
      (node (ref "D8") (pin "A") (pinfunction "A_A") (pintype "passive"))
      (node (ref "IC2") (pin "1") (pinfunction "OUT_1") (pintype "output"))
      (node (ref "R63") (pin "1") (pinfunction "1_1") (pintype "passive"))
    )
    (net (code "21") (name "I_SET") (class "Default")
      (node (ref "R36") (pin "1") (pinfunction "1_1") (pintype "passive"))
      (node (ref "X3") (pin "4") (pinfunction "1_4") (pintype "passive"))
    )
    (net (code "22") (name "I_SET_IN") (class "Default")
      (node (ref "IC6") (pin "3") (pinfunction "VOUTB_3") (pintype "output"))
      (node (ref "IC8") (pin "6") (pinfunction "AIN3/REFN1_6") (pintype "input"))
      (node (ref "X3") (pin "2") (pinfunction "1_2") (pintype "passive"))
    )
    (net (code "23") (name "Net-(C2-Pad2)") (class "Default")
      (node (ref "C2") (pin "2") (pinfunction "2_2") (pintype "passive"))
      (node (ref "R7") (pin "2") (pinfunction "2_2") (pintype "passive"))
    )
    (net (code "24") (name "Net-(C5-Pad1)") (class "Default")
      (node (ref "C5") (pin "1") (pinfunction "1_1") (pintype "passive"))
      (node (ref "R12") (pin "1") (pinfunction "1_1") (pintype "passive"))
    )
    (net (code "25") (name "Net-(C6-Pad2)") (class "Default")
      (node (ref "C6") (pin "2") (pinfunction "2_2") (pintype "passive"))
      (node (ref "R17") (pin "1") (pinfunction "1_1") (pintype "passive"))
    )
    (net (code "26") (name "Net-(C7-Pad2)") (class "Default")
      (node (ref "C7") (pin "2") (pinfunction "2_2") (pintype "passive"))
      (node (ref "R19") (pin "1") (pinfunction "1_1") (pintype "passive"))
    )
    (net (code "27") (name "Net-(C8-Pad1)") (class "Default")
      (node (ref "C8") (pin "1") (pinfunction "1_1") (pintype "passive"))
      (node (ref "R20") (pin "2") (pinfunction "2_2") (pintype "passive"))
      (node (ref "R21") (pin "1") (pinfunction "1_1") (pintype "passive"))
    )
    (net (code "28") (name "Net-(C9-Pad1)") (class "Default")
      (node (ref "C9") (pin "1") (pinfunction "1_1") (pintype "passive"))
      (node (ref "R30") (pin "2") (pinfunction "2_2") (pintype "passive"))
      (node (ref "R31") (pin "1") (pinfunction "1_1") (pintype "passive"))
    )
    (net (code "29") (name "Net-(C10-Pad2)") (class "Default")
      (node (ref "C10") (pin "2") (pinfunction "2_2") (pintype "passive"))
      (node (ref "R28") (pin "1") (pinfunction "1_1") (pintype "passive"))
    )
    (net (code "30") (name "Net-(C11-Pad2)") (class "Default")
      (node (ref "C11") (pin "2") (pinfunction "2_2") (pintype "passive"))
      (node (ref "R29") (pin "1") (pinfunction "1_1") (pintype "passive"))
    )
    (net (code "31") (name "Net-(C12-Pad2)") (class "Default")
      (node (ref "C12") (pin "2") (pinfunction "2_2") (pintype "passive"))
      (node (ref "R33") (pin "1") (pinfunction "1_1") (pintype "passive"))
    )
    (net (code "32") (name "Net-(C23-Pad1)") (class "Default")
      (node (ref "C23") (pin "1") (pinfunction "1_1") (pintype "passive"))
      (node (ref "R45") (pin "1") (pinfunction "1_1") (pintype "passive"))
    )
    (net (code "33") (name "Net-(C24-Pad2)") (class "Default")
      (node (ref "C24") (pin "2") (pinfunction "2_2") (pintype "passive"))
      (node (ref "R46") (pin "1") (pinfunction "1_1") (pintype "passive"))
    )
    (net (code "34") (name "Net-(D1-PadC)") (class "Default")
      (node (ref "D1") (pin "C") (pinfunction "C_C") (pintype "passive"))
      (node (ref "D2") (pin "A") (pinfunction "A_A") (pintype "passive"))
      (node (ref "Q1") (pin "G") (pinfunction "G_G") (pintype "passive"))
      (node (ref "R3") (pin "1") (pinfunction "1_1") (pintype "passive"))
    )
    (net (code "35") (name "Net-(D2-PadC)") (class "Default")
      (node (ref "D2") (pin "C") (pinfunction "C_C") (pintype "passive"))
      (node (ref "ZD3") (pin "C") (pinfunction "C_C") (pintype "passive"))
    )
    (net (code "36") (name "Net-(D3-PadA)") (class "Default")
      (node (ref "D3") (pin "A") (pinfunction "A_A") (pintype "passive"))
      (node (ref "Q2") (pin "C") (pinfunction "C_C") (pintype "passive"))
      (node (ref "Q5") (pin "G") (pinfunction "G_G") (pintype "passive"))
      (node (ref "R6") (pin "2") (pinfunction "2_2") (pintype "passive"))
    )
    (net (code "37") (name "Net-(D3-PadC)") (class "Default")
      (node (ref "D3") (pin "C") (pinfunction "C_C") (pintype "passive"))
      (node (ref "Q6") (pin "2") (pinfunction "C_2") (pintype "passive"))
      (node (ref "Q6") (pin "4") (pinfunction "C_4") (pintype "passive"))
      (node (ref "ZD3") (pin "A") (pinfunction "A_A") (pintype "passive"))
    )
    (net (code "38") (name "Net-(D4-PadC)") (class "Default")
      (node (ref "D4") (pin "C") (pinfunction "C_C") (pintype "passive"))
      (node (ref "Q3") (pin "C") (pinfunction "C_C") (pintype "passive"))
      (node (ref "ZD1") (pin "C") (pinfunction "C_C") (pintype "passive"))
    )
    (net (code "39") (name "Net-(D5-PadA)") (class "Default")
      (node (ref "D5") (pin "A") (pinfunction "A_A") (pintype "passive"))
      (node (ref "D7") (pin "A") (pinfunction "A_A") (pintype "passive"))
      (node (ref "R24") (pin "1") (pinfunction "1_1") (pintype "passive"))
    )
    (net (code "40") (name "Net-(FB-1)") (class "Default")
      (node (ref "FB") (pin "P$1") (pinfunction "1_P$1") (pintype "passive"))
      (node (ref "X2") (pin "2") (pinfunction "KL_2") (pintype "passive"))
    )
    (net (code "41") (name "Net-(IC1A-+IN)") (class "Default")
      (node (ref "IC1") (pin "3") (pinfunction "+IN_3") (pintype "input"))
      (node (ref "R19") (pin "2") (pinfunction "2_2") (pintype "passive"))
      (node (ref "R23") (pin "2") (pinfunction "2_2") (pintype "passive"))
    )
    (net (code "42") (name "Net-(IC1A--IN)") (class "Default")
      (node (ref "C10") (pin "1") (pinfunction "1_1") (pintype "passive"))
      (node (ref "D6") (pin "C") (pinfunction "C_C") (pintype "passive"))
      (node (ref "IC1") (pin "2") (pinfunction "-IN_2") (pintype "input"))
      (node (ref "R25") (pin "2") (pinfunction "2_2") (pintype "passive"))
      (node (ref "R29") (pin "2") (pinfunction "2_2") (pintype "passive"))
    )
    (net (code "43") (name "Net-(IC1B-+IN)") (class "Default")
      (node (ref "IC1") (pin "5") (pinfunction "+IN_5") (pintype "input"))
      (node (ref "R16") (pin "2") (pinfunction "2_2") (pintype "passive"))
      (node (ref "R17") (pin "2") (pinfunction "2_2") (pintype "passive"))
      (node (ref "R20") (pin "1") (pinfunction "1_1") (pintype "passive"))
    )
    (net (code "44") (name "Net-(IC1B--IN)") (class "Default")
      (node (ref "IC1") (pin "6") (pinfunction "-IN_6") (pintype "input"))
      (node (ref "R26") (pin "2") (pinfunction "2_2") (pintype "passive"))
      (node (ref "R30") (pin "1") (pinfunction "1_1") (pintype "passive"))
      (node (ref "R33") (pin "2") (pinfunction "2_2") (pintype "passive"))
    )
    (net (code "45") (name "Net-(IC2A-+IN)") (class "Default")
      (node (ref "IC2") (pin "3") (pinfunction "+IN_3") (pintype "input"))
      (node (ref "R36") (pin "2") (pinfunction "2_2") (pintype "passive"))
    )
    (net (code "46") (name "Net-(IC2A--IN)") (class "Default")
      (node (ref "D8") (pin "C") (pinfunction "C_C") (pintype "passive"))
      (node (ref "IC2") (pin "2") (pinfunction "-IN_2") (pintype "input"))
      (node (ref "R39") (pin "2") (pinfunction "2_2") (pintype "passive"))
      (node (ref "R45") (pin "2") (pinfunction "2_2") (pintype "passive"))
      (node (ref "R46") (pin "2") (pinfunction "2_2") (pintype "passive"))
    )
    (net (code "47") (name "Net-(IC2B--IN)") (class "Default")
      (node (ref "IC2") (pin "6") (pinfunction "-IN_6") (pintype "input"))
      (node (ref "IC2") (pin "7") (pinfunction "OUT_7") (pintype "output"))
    )
    (net (code "48") (name "Net-(IC3A-+IN)") (class "Default")
      (node (ref "IC3") (pin "3") (pinfunction "+IN_3") (pintype "input"))
      (node (ref "R35") (pin "2") (pinfunction "2_2") (pintype "passive"))
      (node (ref "R37") (pin "2") (pinfunction "2_2") (pintype "passive"))
    )
    (net (code "49") (name "Net-(IC3A--IN)") (class "Default")
      (node (ref "IC3") (pin "2") (pinfunction "-IN_2") (pintype "input"))
      (node (ref "R41") (pin "2") (pinfunction "2_2") (pintype "passive"))
      (node (ref "R44") (pin "1") (pinfunction "1_1") (pintype "passive"))
    )
    (net (code "50") (name "Net-(IC4A-+IN)") (class "Default")
      (node (ref "IC4") (pin "5") (pinfunction "+IN_5") (pintype "input"))
      (node (ref "IC4") (pin "6") (pinfunction "-IN_6") (pintype "input"))
      (node (ref "R51") (pin "2") (pinfunction "2_2") (pintype "passive"))
    )
    (net (code "51") (name "Net-(IC4A--IN)") (class "Default")
      (node (ref "IC4") (pin "10") (pinfunction "-IN_10") (pintype "input"))
      (node (ref "IC4") (pin "4") (pinfunction "-IN_4") (pintype "input"))
      (node (ref "R59") (pin "1") (pinfunction "1_1") (pintype "passive"))
      (node (ref "R61") (pin "2") (pinfunction "2_2") (pintype "passive"))
    )
    (net (code "52") (name "Net-(IC4A-OUT)") (class "Default")
      (node (ref "IC4") (pin "1") (pinfunction "OUT_1") (pintype "open_collector"))
      (node (ref "IC4") (pin "2") (pinfunction "OUT_2") (pintype "open_collector"))
      (node (ref "R55") (pin "1") (pinfunction "1_1") (pintype "passive"))
    )
    (net (code "53") (name "Net-(IC4B-+IN)") (class "Default")
      (node (ref "IC4") (pin "7") (pinfunction "+IN_7") (pintype "input"))
      (node (ref "IC4") (pin "9") (pinfunction "+IN_9") (pintype "input"))
      (node (ref "R54") (pin "1") (pinfunction "1_1") (pintype "passive"))
      (node (ref "R56") (pin "2") (pinfunction "2_2") (pintype "passive"))
    )
    (net (code "54") (name "Net-(IC4C--IN)") (class "Default")
      (node (ref "IC4") (pin "11") (pinfunction "+IN_11") (pintype "input"))
      (node (ref "IC4") (pin "8") (pinfunction "-IN_8") (pintype "input"))
      (node (ref "R63") (pin "2") (pinfunction "2_2") (pintype "passive"))
    )
    (net (code "55") (name "Net-(IC4C-OUT)") (class "Default")
      (node (ref "IC4") (pin "13") (pinfunction "OUT_13") (pintype "open_collector"))
      (node (ref "IC4") (pin "14") (pinfunction "OUT_14") (pintype "open_collector"))
      (node (ref "R62") (pin "1") (pinfunction "1_1") (pintype "passive"))
    )
    (net (code "56") (name "Net-(IC5-GP0)") (class "Default")
      (node (ref "IC5") (pin "10") (pinfunction "GP0_10") (pintype "bidirectional"))
      (node (ref "JP1") (pin "1") (pinfunction "1_1") (pintype "passive"))
    )
    (net (code "57") (name "Net-(IC5-GP4)") (class "Default")
      (node (ref "IC5") (pin "14") (pinfunction "GP4_14") (pintype "bidirectional"))
      (node (ref "X8") (pin "2") (pinfunction "S_2") (pintype "passive"))
    )
    (net (code "58") (name "Net-(IC5-INT)") (class "Default")
      (node (ref "IC5") (pin "8") (pinfunction "INT_8") (pintype "output"))
      (node (ref "JP1") (pin "4") (pinfunction "4_4") (pintype "passive"))
    )
    (net (code "59") (name "Net-(IC7-TRIM{slash}NR)") (class "Default")
      (node (ref "C33") (pin "1") (pinfunction "1_1") (pintype "passive"))
      (node (ref "IC7") (pin "5") (pinfunction "TRIM/NR_5") (pintype "input"))
    )
    (net (code "60") (name "Net-(IC8-AVDD)") (class "Default")
      (node (ref "C36") (pin "2") (pinfunction "2_2") (pintype "passive"))
      (node (ref "C37") (pin "2") (pinfunction "2_2") (pintype "passive"))
      (node (ref "IC8") (pin "12") (pinfunction "AVDD_12") (pintype "power_in"))
      (node (ref "R64") (pin "2") (pinfunction "2_2") (pintype "passive"))
    )
    (net (code "61") (name "Net-(Q1-PadS)") (class "Default")
      (node (ref "Q1") (pin "S") (pinfunction "S_S") (pintype "passive"))
      (node (ref "R1") (pin "2") (pinfunction "2_2") (pintype "passive"))
      (node (ref "R3") (pin "2") (pinfunction "2_2") (pintype "passive"))
      (node (ref "R4") (pin "2") (pinfunction "2_2") (pintype "passive"))
      (node (ref "R8") (pin "2") (pinfunction "2_2") (pintype "passive"))
      (node (ref "ZD1") (pin "A") (pinfunction "A_A") (pintype "passive"))
    )
    (net (code "62") (name "Net-(Q2-PadB)") (class "Default")
      (node (ref "Q2") (pin "B") (pinfunction "B_B") (pintype "passive"))
      (node (ref "R5") (pin "2") (pinfunction "2_2") (pintype "passive"))
    )
    (net (code "63") (name "Net-(Q3-PadB)") (class "Default")
      (node (ref "Q3") (pin "B") (pinfunction "B_B") (pintype "passive"))
      (node (ref "R4") (pin "1") (pinfunction "1_1") (pintype "passive"))
    )
    (net (code "64") (name "Net-(Q4-B)") (class "Default")
      (node (ref "D4") (pin "A") (pinfunction "A_A") (pintype "passive"))
      (node (ref "Q4") (pin "1") (pinfunction "B_1") (pintype "passive"))
      (node (ref "R12") (pin "2") (pinfunction "2_2") (pintype "passive"))
      (node (ref "R15") (pin "1") (pinfunction "1_1") (pintype "passive"))
    )
    (net (code "65") (name "Net-(Q4-E)") (class "Default")
      (node (ref "D1") (pin "A") (pinfunction "A_A") (pintype "passive"))
      (node (ref "Q4") (pin "3") (pinfunction "E_3") (pintype "passive"))
    )
    (net (code "66") (name "Net-(Q5-PadS)") (class "Default")
      (node (ref "Q5") (pin "S") (pinfunction "S_S") (pintype "passive"))
      (node (ref "R2") (pin "1") (pinfunction "1_1") (pintype "passive"))
      (node (ref "R5") (pin "1") (pinfunction "1_1") (pintype "passive"))
      (node (ref "R6") (pin "1") (pinfunction "1_1") (pintype "passive"))
    )
    (net (code "67") (name "Net-(Q6-E)") (class "Default")
      (node (ref "Q6") (pin "3") (pinfunction "E_3") (pintype "passive"))
      (node (ref "R14") (pin "1") (pinfunction "1_1") (pintype "passive"))
    )
    (net (code "68") (name "Net-(Q7-PadE)") (class "Default")
      (node (ref "Q7") (pin "E") (pinfunction "E_E") (pintype "passive"))
      (node (ref "R10") (pin "1") (pinfunction "1_1") (pintype "passive"))
    )
    (net (code "69") (name "Net-(Q8-PadC)") (class "Default")
      (node (ref "Q8") (pin "C") (pinfunction "C_C") (pintype "passive"))
      (node (ref "Q9") (pin "C") (pinfunction "C_C") (pintype "passive"))
      (node (ref "R15") (pin "2") (pinfunction "2_2") (pintype "passive"))
      (node (ref "R22") (pin "2") (pinfunction "2_2") (pintype "passive"))
    )
    (net (code "70") (name "Net-(Q8-PadE)") (class "Default")
      (node (ref "Q8") (pin "E") (pinfunction "E_E") (pintype "passive"))
      (node (ref "R11") (pin "1") (pinfunction "1_1") (pintype "passive"))
    )
    (net (code "71") (name "Net-(Q9-PadB)") (class "Default")
      (node (ref "Q9") (pin "B") (pinfunction "B_B") (pintype "passive"))
      (node (ref "R18") (pin "2") (pinfunction "2_2") (pintype "passive"))
      (node (ref "R8") (pin "1") (pinfunction "1_1") (pintype "passive"))
    )
    (net (code "72") (name "Net-(Q9-PadE)") (class "Default")
      (node (ref "Q9") (pin "E") (pinfunction "E_E") (pintype "passive"))
      (node (ref "R24") (pin "2") (pinfunction "2_2") (pintype "passive"))
    )
    (net (code "73") (name "Net-(Q10-PadC)") (class "Default")
      (node (ref "Q10") (pin "C") (pinfunction "C_C") (pintype "passive"))
      (node (ref "Q7") (pin "B") (pinfunction "B_B") (pintype "passive"))
      (node (ref "Q7") (pin "C") (pinfunction "C_C") (pintype "passive"))
      (node (ref "Q8") (pin "B") (pinfunction "B_B") (pintype "passive"))
    )
    (net (code "74") (name "Net-(Q10-PadE)") (class "Default")
      (node (ref "Q10") (pin "E") (pinfunction "E_E") (pintype "passive"))
      (node (ref "R27") (pin "2") (pinfunction "2_2") (pintype "passive"))
    )
    (net (code "75") (name "Net-(Q12-D)") (class "Default")
      (node (ref "Q12") (pin "3") (pinfunction "D_3") (pintype "passive"))
      (node (ref "R50") (pin "2") (pinfunction "2_2") (pintype "passive"))
      (node (ref "R52") (pin "2") (pinfunction "2_2") (pintype "passive"))
    )
    (net (code "76") (name "Net-(Q12-G)") (class "Default")
      (node (ref "D11") (pin "A") (pinfunction "A_A") (pintype "passive"))
      (node (ref "Q12") (pin "1") (pinfunction "G_1") (pintype "passive"))
      (node (ref "R49") (pin "2") (pinfunction "2_2") (pintype "passive"))
      (node (ref "X5") (pin "3") (pinfunction "S_3") (pintype "passive"))
    )
    (net (code "77") (name "Net-(Q13-D)") (class "Default")
      (node (ref "Q13") (pin "3") (pinfunction "D_3") (pintype "passive"))
      (node (ref "R58") (pin "2") (pinfunction "2_2") (pintype "passive"))
    )
    (net (code "78") (name "Net-(Q14-D)") (class "Default")
      (node (ref "Q14") (pin "3") (pinfunction "D_3") (pintype "passive"))
      (node (ref "R57") (pin "1") (pinfunction "1_1") (pintype "passive"))
    )
    (net (code "79") (name "Net-(R34-Pad2)") (class "Default")
      (node (ref "R34") (pin "2") (pinfunction "2_2") (pintype "passive"))
      (node (ref "R35") (pin "1") (pinfunction "1_1") (pintype "passive"))
    )
    (net (code "80") (name "Net-(R37-Pad1)") (class "Default")
      (node (ref "R37") (pin "1") (pinfunction "1_1") (pintype "passive"))
      (node (ref "R38") (pin "2") (pinfunction "2_2") (pintype "passive"))
    )
    (net (code "81") (name "Net-(R41-Pad1)") (class "Default")
      (node (ref "R41") (pin "1") (pinfunction "1_1") (pintype "passive"))
      (node (ref "R42") (pin "2") (pinfunction "2_2") (pintype "passive"))
    )
    (net (code "82") (name "Net-(R43-Pad1)") (class "Default")
      (node (ref "R43") (pin "1") (pinfunction "1_1") (pintype "passive"))
      (node (ref "R44") (pin "2") (pinfunction "2_2") (pintype "passive"))
    )
    (net (code "83") (name "Net-(X2F-KL)") (class "Default")
      (node (ref "C3") (pin "1") (pinfunction "1_1") (pintype "passive"))
      (node (ref "Q1") (pin "D") (pinfunction "D_D") (pintype "passive"))
      (node (ref "X2") (pin "14") (pinfunction "KL_14") (pintype "passive"))
      (node (ref "X2") (pin "15") (pinfunction "KL_15") (pintype "passive"))
      (node (ref "X2") (pin "16") (pinfunction "KL_16") (pintype "passive"))
      (node (ref "X2") (pin "17") (pinfunction "KL_17") (pintype "passive"))
    )
    (net (code "84") (name "Net-(X2J-KL)") (class "Default")
      (node (ref "C4") (pin "1") (pinfunction "1_1") (pintype "passive"))
      (node (ref "Q4") (pin "2") (pinfunction "C_2") (pintype "passive"))
      (node (ref "Q4") (pin "4") (pinfunction "C_4") (pintype "passive"))
      (node (ref "R10") (pin "2") (pinfunction "2_2") (pintype "passive"))
      (node (ref "R11") (pin "2") (pinfunction "2_2") (pintype "passive"))
      (node (ref "X2") (pin "18") (pinfunction "KL_18") (pintype "passive"))
    )
    (net (code "85") (name "Net-(X4B-S)") (class "Default")
      (node (ref "D10") (pin "C") (pinfunction "C_C") (pintype "passive"))
      (node (ref "X4") (pin "2") (pinfunction "S_2") (pintype "passive"))
    )
    (net (code "86") (name "Net-(X4D-S)") (class "Default")
      (node (ref "R47") (pin "1") (pinfunction "1_1") (pintype "passive"))
      (node (ref "X4") (pin "4") (pinfunction "S_4") (pintype "passive"))
    )
    (net (code "87") (name "Net-(X5A-S)") (class "Default")
      (node (ref "R52") (pin "1") (pinfunction "1_1") (pintype "passive"))
      (node (ref "X5") (pin "1") (pinfunction "S_1") (pintype "passive"))
    )
    (net (code "88") (name "Net-(X6A-S)") (class "Default")
      (node (ref "R57") (pin "2") (pinfunction "2_2") (pintype "passive"))
      (node (ref "X6") (pin "1") (pinfunction "S_1") (pintype "passive"))
    )
    (net (code "89") (name "Net-(X6C-S)") (class "Default")
      (node (ref "R58") (pin "1") (pinfunction "1_1") (pintype "passive"))
      (node (ref "X6") (pin "3") (pinfunction "S_3") (pintype "passive"))
    )
    (net (code "90") (name "OE_DRIVE") (class "Default")
      (node (ref "Q11") (pin "3") (pinfunction "D_3") (pintype "passive"))
      (node (ref "R27") (pin "1") (pinfunction "1_1") (pintype "passive"))
      (node (ref "R47") (pin "2") (pinfunction "2_2") (pintype "passive"))
    )
    (net (code "91") (name "OUT+") (class "Default")
      (node (ref "C1") (pin "1") (pinfunction "+_1") (pintype "passive"))
      (node (ref "C1") (pin "1.1") (pinfunction "+_1.1") (pintype "passive"))
      (node (ref "C11") (pin "1") (pinfunction "1_1") (pintype "passive"))
      (node (ref "C2") (pin "1") (pinfunction "1_1") (pintype "passive"))
      (node (ref "C24") (pin "1") (pinfunction "1_1") (pintype "passive"))
      (node (ref "C8") (pin "2") (pinfunction "2_2") (pintype "passive"))
      (node (ref "Q2") (pin "E") (pinfunction "E_E") (pintype "passive"))
      (node (ref "Q3") (pin "E") (pinfunction "E_E") (pintype "passive"))
      (node (ref "R1") (pin "1") (pinfunction "1_1") (pintype "passive"))
      (node (ref "R2") (pin "2") (pinfunction "2_2") (pintype "passive"))
      (node (ref "R9") (pin "1") (pinfunction "1_1") (pintype "passive"))
      (node (ref "X1") (pin "P$1") (pinfunction "1_P$1") (pintype "bidirectional"))
      (node (ref "X2") (pin "9") (pinfunction "KL_9") (pintype "passive"))
      (node (ref "ZD2") (pin "C") (pinfunction "1_C") (pintype "passive"))
    )
    (net (code "92") (name "OUT-") (class "Default")
      (node (ref "C1") (pin "2") (pinfunction "-_2") (pintype "passive"))
      (node (ref "C1") (pin "2.1") (pinfunction "-_2.1") (pintype "passive"))
      (node (ref "C7") (pin "1") (pinfunction "1_1") (pintype "passive"))
      (node (ref "C9") (pin "2") (pinfunction "2_2") (pintype "passive"))
      (node (ref "R32") (pin "2") (pinfunction "2_2") (pintype "passive"))
      (node (ref "R38") (pin "1") (pinfunction "1_1") (pintype "passive"))
      (node (ref "R40") (pin "1") (pinfunction "1_1") (pintype "passive"))
      (node (ref "R7") (pin "1") (pinfunction "1_1") (pintype "passive"))
      (node (ref "X1") (pin "P$2") (pinfunction "1_P$2") (pintype "bidirectional"))
      (node (ref "ZD2") (pin "A") (pinfunction "2_A") (pintype "passive"))
    )
    (net (code "93") (name "PGND") (class "Default")
      (node (ref "C13") (pin "1") (pinfunction "1_1") (pintype "passive"))
      (node (ref "C14") (pin "2") (pinfunction "2_2") (pintype "passive"))
      (node (ref "C15") (pin "1") (pinfunction "1_1") (pintype "passive"))
      (node (ref "C16") (pin "1") (pinfunction "1_1") (pintype "passive"))
      (node (ref "C17") (pin "1") (pinfunction "1_1") (pintype "passive"))
      (node (ref "C18") (pin "1") (pinfunction "1_1") (pintype "passive"))
      (node (ref "C19") (pin "1") (pinfunction "1_1") (pintype "passive"))
      (node (ref "C20") (pin "2") (pinfunction "2_2") (pintype "passive"))
      (node (ref "C21") (pin "1") (pinfunction "1_1") (pintype "passive"))
      (node (ref "C22") (pin "1") (pinfunction "1_1") (pintype "passive"))
      (node (ref "C25") (pin "1") (pinfunction "1_1") (pintype "passive"))
      (node (ref "C26") (pin "1") (pinfunction "1_1") (pintype "passive"))
      (node (ref "C27") (pin "2") (pinfunction "2_2") (pintype "passive"))
      (node (ref "C28") (pin "2") (pinfunction "2_2") (pintype "passive"))
      (node (ref "C29") (pin "1") (pinfunction "1_1") (pintype "passive"))
      (node (ref "C3") (pin "2") (pinfunction "2_2") (pintype "passive"))
      (node (ref "C30") (pin "1") (pinfunction "1_1") (pintype "passive"))
      (node (ref "C31") (pin "2") (pinfunction "2_2") (pintype "passive"))
      (node (ref "C32") (pin "2") (pinfunction "2_2") (pintype "passive"))
      (node (ref "C33") (pin "2") (pinfunction "2_2") (pintype "passive"))
      (node (ref "C34") (pin "1") (pinfunction "1_1") (pintype "passive"))
      (node (ref "C35") (pin "1") (pinfunction "1_1") (pintype "passive"))
      (node (ref "C36") (pin "1") (pinfunction "1_1") (pintype "passive"))
      (node (ref "C37") (pin "1") (pinfunction "1_1") (pintype "passive"))
      (node (ref "C4") (pin "2") (pinfunction "2_2") (pintype "passive"))
      (node (ref "C5") (pin "2") (pinfunction "2_2") (pintype "passive"))
      (node (ref "IC2") (pin "5") (pinfunction "+IN_5") (pintype "input"))
      (node (ref "IC5") (pin "4") (pinfunction "A1_4") (pintype "input"))
      (node (ref "IC5") (pin "5") (pinfunction "A0_5") (pintype "input"))
      (node (ref "IC5") (pin "9") (pinfunction "VSS_9") (pintype "power_in"))
      (node (ref "IC6") (pin "8") (pinfunction "GND_8") (pintype "power_in"))
      (node (ref "IC7") (pin "4") (pinfunction "GND_4") (pintype "passive"))
      (node (ref "IC8") (pin "3") (pinfunction "CLK_3") (pintype "bidirectional"))
      (node (ref "IC8") (pin "4") (pinfunction "DGND_4") (pintype "power_in"))
      (node (ref "IC8") (pin "5") (pinfunction "AVSS_5") (pintype "power_in"))
      (node (ref "IC8") (pin "8") (pinfunction "REFN0_8") (pintype "input"))
      (node (ref "Q11") (pin "2") (pinfunction "S_2") (pintype "passive"))
      (node (ref "Q13") (pin "2") (pinfunction "S_2") (pintype "passive"))
      (node (ref "Q14") (pin "2") (pinfunction "S_2") (pintype "passive"))
      (node (ref "Q5") (pin "D") (pinfunction "D_D") (pintype "passive"))
      (node (ref "R16") (pin "1") (pinfunction "1_1") (pintype "passive"))
      (node (ref "R18") (pin "1") (pinfunction "1_1") (pintype "passive"))
      (node (ref "R22") (pin "1") (pinfunction "1_1") (pintype "passive"))
      (node (ref "R34") (pin "1") (pinfunction "1_1") (pintype "passive"))
      (node (ref "R48") (pin "1") (pinfunction "1_1") (pintype "passive"))
      (node (ref "R56") (pin "1") (pinfunction "1_1") (pintype "passive"))
      (node (ref "R59") (pin "2") (pinfunction "2_2") (pintype "passive"))
      (node (ref "SH1") (pin "1") (pinfunction "GND_A_1") (pintype "bidirectional"))
      (node (ref "X2") (pin "12") (pinfunction "KL_12") (pintype "passive"))
      (node (ref "X3") (pin "5") (pinfunction "1_5") (pintype "passive"))
      (node (ref "X3") (pin "6") (pinfunction "1_6") (pintype "passive"))
      (node (ref "X5") (pin "2") (pinfunction "S_2") (pintype "passive"))
      (node (ref "X7") (pin "10") (pinfunction "KL_10") (pintype "passive"))
      (node (ref "X8") (pin "3") (pinfunction "S_3") (pintype "passive"))
    )
    (net (code "94") (name "POUT-") (class "Default")
      (node (ref "R40") (pin "2") (pinfunction "2_2") (pintype "passive"))
      (node (ref "R42") (pin "1") (pinfunction "1_1") (pintype "passive"))
      (node (ref "SH1") (pin "2") (pinfunction "GND_B_2") (pintype "bidirectional"))
      (node (ref "X2") (pin "10") (pinfunction "KL_10") (pintype "passive"))
      (node (ref "X2") (pin "11") (pinfunction "KL_11") (pintype "passive"))
      (node (ref "X2") (pin "13") (pinfunction "KL_13") (pintype "passive"))
    )
    (net (code "95") (name "PREG_EN") (class "Default")
      (node (ref "D9") (pin "C") (pinfunction "C_C") (pintype "passive"))
      (node (ref "Q11") (pin "1") (pinfunction "G_1") (pintype "passive"))
      (node (ref "R48") (pin "2") (pinfunction "2_2") (pintype "passive"))
      (node (ref "X2") (pin "5") (pinfunction "KL_5") (pintype "passive"))
      (node (ref "X4") (pin "1") (pinfunction "S_1") (pintype "passive"))
    )
    (net (code "96") (name "PWRGOOD") (class "Default")
      (node (ref "D10") (pin "A") (pinfunction "A_A") (pintype "passive"))
      (node (ref "IC5") (pin "16") (pinfunction "GP6_16") (pintype "bidirectional"))
      (node (ref "X2") (pin "1") (pinfunction "KL_1") (pintype "passive"))
    )
    (net (code "97") (name "SET_OE") (class "Default")
      (node (ref "D9") (pin "A") (pinfunction "A_A") (pintype "passive"))
      (node (ref "IC5") (pin "17") (pinfunction "GP7_17") (pintype "bidirectional"))
    )
    (net (code "98") (name "TEMP_FREQ") (class "Default")
      (node (ref "IC5") (pin "13") (pinfunction "GP3_13") (pintype "bidirectional"))
      (node (ref "X2") (pin "3") (pinfunction "KL_3") (pintype "passive"))
    )
    (net (code "99") (name "U_MON") (class "Default")
      (node (ref "IC1") (pin "7") (pinfunction "OUT_7") (pintype "output"))
      (node (ref "IC8") (pin "10") (pinfunction "AIN1_10") (pintype "input"))
      (node (ref "R25") (pin "1") (pinfunction "1_1") (pintype "passive"))
      (node (ref "R26") (pin "1") (pinfunction "1_1") (pintype "passive"))
    )
    (net (code "100") (name "U_SERVO") (class "Default")
      (node (ref "D5") (pin "C") (pinfunction "C_C") (pintype "passive"))
      (node (ref "D6") (pin "A") (pinfunction "A_A") (pintype "passive"))
      (node (ref "IC1") (pin "1") (pinfunction "OUT_1") (pintype "output"))
      (node (ref "R28") (pin "2") (pinfunction "2_2") (pintype "passive"))
      (node (ref "R51") (pin "1") (pinfunction "1_1") (pintype "passive"))
    )
    (net (code "101") (name "U_SET") (class "Default")
      (node (ref "R23") (pin "1") (pinfunction "1_1") (pintype "passive"))
      (node (ref "X3") (pin "3") (pinfunction "1_3") (pintype "passive"))
    )
    (net (code "102") (name "U_SET_IN") (class "Default")
      (node (ref "IC6") (pin "4") (pinfunction "VOUTA_4") (pintype "output"))
      (node (ref "IC8") (pin "11") (pinfunction "AIN0/REFP1_11") (pintype "input"))
      (node (ref "X3") (pin "1") (pinfunction "1_1") (pintype "passive"))
    )
    (net (code "103") (name "V+") (class "Default")
      (node (ref "C13") (pin "2") (pinfunction "2_2") (pintype "passive"))
      (node (ref "C14") (pin "1") (pinfunction "1_1") (pintype "passive"))
      (node (ref "C15") (pin "2") (pinfunction "2_2") (pintype "passive"))
      (node (ref "C16") (pin "2") (pinfunction "2_2") (pintype "passive"))
      (node (ref "C17") (pin "2") (pinfunction "2_2") (pintype "passive"))
      (node (ref "C25") (pin "2") (pinfunction "2_2") (pintype "passive"))
      (node (ref "IC1") (pin "8") (pinfunction "V+_8") (pintype "power_in"))
      (node (ref "IC2") (pin "8") (pinfunction "V+_8") (pintype "power_in"))
      (node (ref "IC3") (pin "7") (pinfunction "V+_7") (pintype "power_in"))
      (node (ref "IC4") (pin "3") (pinfunction "V+_3") (pintype "power_in"))
      (node (ref "R54") (pin "2") (pinfunction "2_2") (pintype "passive"))
      (node (ref "X2") (pin "6") (pinfunction "KL_6") (pintype "passive"))
    )
    (net (code "104") (name "V-") (class "Default")
      (node (ref "C18") (pin "2") (pinfunction "2_2") (pintype "passive"))
      (node (ref "C19") (pin "2") (pinfunction "2_2") (pintype "passive"))
      (node (ref "C20") (pin "1") (pinfunction "1_1") (pintype "passive"))
      (node (ref "C21") (pin "2") (pinfunction "2_2") (pintype "passive"))
      (node (ref "C22") (pin "2") (pinfunction "2_2") (pintype "passive"))
      (node (ref "C26") (pin "2") (pinfunction "2_2") (pintype "passive"))
      (node (ref "IC1") (pin "4") (pinfunction "V-_4") (pintype "power_in"))
      (node (ref "IC2") (pin "4") (pinfunction "V-_4") (pintype "power_in"))
      (node (ref "IC3") (pin "4") (pinfunction "V-_4") (pintype "power_in"))
      (node (ref "IC4") (pin "12") (pinfunction "GND_12") (pintype "power_in"))
      (node (ref "R61") (pin "1") (pinfunction "1_1") (pintype "passive"))
      (node (ref "X2") (pin "4") (pinfunction "KL_4") (pintype "passive"))
    )
    (net (code "105") (name "unconnected-(IC7-TEMP-Pad3)") (class "Default")
      (node (ref "IC7") (pin "3") (pinfunction "TEMP_3") (pintype "input"))
    )
  )
)
